# esptoy_v12.net
KiCad netlist of a schematic drawn in EAGLE
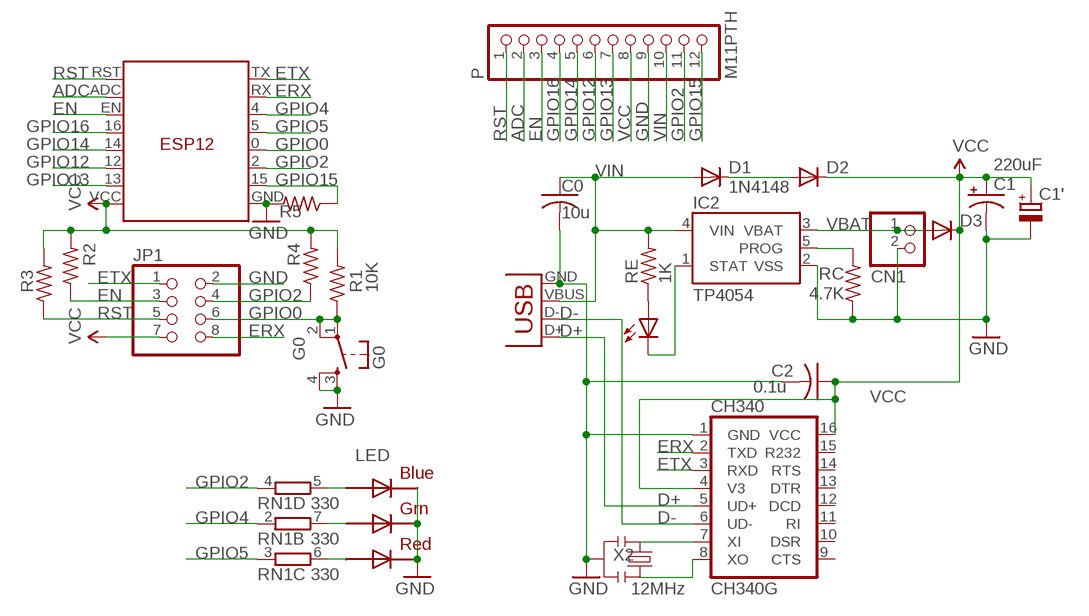
[diagram p0: schematic, sheet 1]

(export (version "E")
  (design (tool "Eeschema 10.0.6"))
  (components
    (comp (ref "C0")
      (value "10u")
      (footprint "eagle-import:C0805K")
      (libsource (lib "eagle-import") (part "adafruit2013_C-USC0805K"))
    )
    (comp (ref "C1")
      (value "220uF")
      (footprint "eagle-import:EIA3528-KIT")
      (libsource (lib "eagle-import") (part "CAP_POL3528-KIT"))
    )
    (comp (ref "C1'")
      (value "CPOL-EUD")
      (footprint "eagle-import:PANASONIC_D")
      (libsource (lib "eagle-import") (part "CPOL-EUD"))
    )
    (comp (ref "C2")
      (value "0.1u")
      (footprint "eagle-import:C0603K")
      (libsource (lib "eagle-import") (part "C-USC0603K"))
    )
    (comp (ref "CH340")
      (value "CH340G")
      (footprint "eagle-import:SO16")
      (libsource (lib "eagle-import") (part "CH340G"))
    )
    (comp (ref "CHG")
      (value "0805")
      (footprint "eagle-import:CHIPLED_0805")
      (libsource (lib "eagle-import") (part "LEDCHIPLED_0805"))
    )
    (comp (ref "CN1")
      (value "JST_2PIN-SMT-RA")
      (footprint "eagle-import:JST-PH-2-SMT-RA")
      (libsource (lib "eagle-import") (part "JST_2PIN-SMT-RA"))
    )
    (comp (ref "D1")
      (value "1N4148")
      (footprint "eagle-import:MINIMELF")
      (libsource (lib "eagle-import") (part "DIODE-MINIMELF"))
    )
    (comp (ref "D2")
      (value "DIODE-MINIMELF")
      (footprint "eagle-import:MINIMELF")
      (libsource (lib "eagle-import") (part "DIODE-MINIMELF"))
    )
    (comp (ref "D3")
      (value "DIODE-MINIMELF")
      (footprint "eagle-import:MINIMELF")
      (libsource (lib "eagle-import") (part "DIODE-MINIMELF"))
    )
    (comp (ref "G0")
      (value "G0")
      (footprint "eagle-import:TACTILE_SWITCH_SMD")
      (libsource (lib "eagle-import") (part "TAC_SWITCHSMD"))
    )
    (comp (ref "IC2")
      (value "TP4054")
      (footprint "eagle-import:SOT23-5")
      (libsource (lib "eagle-import") (part "MCP73831"))
    )
    (comp (ref "JP1")
      (value "PINHD-2X4")
      (footprint "eagle-import:2X04")
      (libsource (lib "eagle-import") (part "PINHD-2X4"))
    )
    (comp (ref "LED")
      (value "RGBLED5050")
      (footprint "eagle-import:RGBLED5050")
      (libsource (lib "eagle-import") (part "RGBLED5050"))
    )
    (comp (ref "P")
      (value "M11PTH")
      (footprint "eagle-import:1X12-CB")
      (libsource (lib "eagle-import") (part "PINHD-1X12-CB"))
    )
    (comp (ref "R1")
      (value "10K")
      (footprint "eagle-import:R0603")
      (libsource (lib "eagle-import") (part "R-US_R0603"))
    )
    (comp (ref "R2")
      (value "R-US_R0603")
      (footprint "eagle-import:R0603")
      (libsource (lib "eagle-import") (part "R-US_R0603"))
    )
    (comp (ref "R3")
      (value "R-US_R0603")
      (footprint "eagle-import:R0603")
      (libsource (lib "eagle-import") (part "R-US_R0603"))
    )
    (comp (ref "R4")
      (value "R-US_R0603")
      (footprint "eagle-import:R0603")
      (libsource (lib "eagle-import") (part "R-US_R0603"))
    )
    (comp (ref "R5")
      (value "R-US_R0603")
      (footprint "eagle-import:R0603")
      (libsource (lib "eagle-import") (part "R-US_R0603"))
    )
    (comp (ref "RC")
      (value "4.7K")
      (footprint "eagle-import:R0805")
      (libsource (lib "eagle-import") (part "adafruit2013_R-US_R0805"))
    )
    (comp (ref "RE")
      (value "1K")
      (footprint "eagle-import:R0603")
      (libsource (lib "eagle-import") (part "R-US_R0603"))
    )
    (comp (ref "RN1")
      (value "330")
      (footprint "eagle-import:EXB38V")
      (libsource (lib "eagle-import") (part "4R-NEXB38V"))
    )
    (comp (ref "U$1")
      (value "ESP12")
      (footprint "eagle-import:ESP12")
      (libsource (lib "eagle-import") (part "ESP12"))
    )
    (comp (ref "X2")
      (value "12MHz")
      (footprint "eagle-import:RESONATOR-SMD")
      (libsource (lib "eagle-import") (part "RESONATORSMD"))
    )
    (comp (ref "X3")
      (value "USB-MICROB")
      (footprint "eagle-import:USB-MICROB")
      (libsource (lib "eagle-import") (part "USB-MICROB"))
    )
  )
  (nets
    (net (code "1") (name "/ADC") (class "Default")
      (node (ref "P") (pin "2") (pinfunction "2_2") (pintype "passive"))
      (node (ref "U$1") (pin "ADC") (pinfunction "ADC_ADC") (pintype "bidirectional"))
    )
    (net (code "2") (name "/D+") (class "Default")
      (node (ref "CH340") (pin "5") (pinfunction "UD+_5") (pintype "bidirectional"))
      (node (ref "X3") (pin "D+") (pinfunction "D+_D+") (pintype "bidirectional"))
    )
    (net (code "3") (name "/D-") (class "Default")
      (node (ref "CH340") (pin "6") (pinfunction "UD-_6") (pintype "bidirectional"))
      (node (ref "X3") (pin "D-") (pinfunction "D-_D-") (pintype "bidirectional"))
    )
    (net (code "4") (name "/EN") (class "Default")
      (node (ref "JP1") (pin "3") (pinfunction "3_3") (pintype "passive"))
      (node (ref "P") (pin "3") (pinfunction "3_3") (pintype "passive"))
      (node (ref "R2") (pin "1") (pinfunction "1_1") (pintype "passive"))
      (node (ref "U$1") (pin "EN") (pinfunction "EN_EN") (pintype "bidirectional"))
    )
    (net (code "5") (name "/ERX") (class "Default")
      (node (ref "CH340") (pin "2") (pinfunction "TXD_2") (pintype "bidirectional"))
      (node (ref "JP1") (pin "8") (pinfunction "8_8") (pintype "passive"))
      (node (ref "U$1") (pin "RX") (pinfunction "RX_RX") (pintype "bidirectional"))
    )
    (net (code "6") (name "/ETX") (class "Default")
      (node (ref "CH340") (pin "3") (pinfunction "RXD_3") (pintype "bidirectional"))
      (node (ref "JP1") (pin "1") (pinfunction "1_1") (pintype "passive"))
      (node (ref "U$1") (pin "TX") (pinfunction "TX_TX") (pintype "bidirectional"))
    )
    (net (code "7") (name "/GPIO0") (class "Default")
      (node (ref "G0") (pin "1") (pinfunction "1_1") (pintype "passive"))
      (node (ref "G0") (pin "2") (pinfunction "2_2") (pintype "passive"))
      (node (ref "JP1") (pin "6") (pinfunction "6_6") (pintype "passive"))
      (node (ref "R1") (pin "1") (pinfunction "1_1") (pintype "passive"))
      (node (ref "U$1") (pin "0") (pinfunction "G0_0") (pintype "bidirectional"))
    )
    (net (code "8") (name "/GPIO2") (class "Default")
      (node (ref "JP1") (pin "4") (pinfunction "4_4") (pintype "passive"))
      (node (ref "P") (pin "11") (pinfunction "11_11") (pintype "passive"))
      (node (ref "R4") (pin "1") (pinfunction "1_1") (pintype "passive"))
      (node (ref "RN1") (pin "4") (pinfunction "1_4") (pintype "passive"))
      (node (ref "U$1") (pin "2") (pinfunction "G2_2") (pintype "bidirectional"))
    )
    (net (code "9") (name "/GPIO4") (class "Default")
      (node (ref "RN1") (pin "2") (pinfunction "1_2") (pintype "passive"))
      (node (ref "U$1") (pin "4") (pinfunction "G4_4") (pintype "bidirectional"))
    )
    (net (code "10") (name "/GPIO5") (class "Default")
      (node (ref "RN1") (pin "3") (pinfunction "1_3") (pintype "passive"))
      (node (ref "U$1") (pin "5") (pinfunction "G5_5") (pintype "bidirectional"))
    )
    (net (code "11") (name "/GPIO12") (class "Default")
      (node (ref "P") (pin "6") (pinfunction "6_6") (pintype "passive"))
      (node (ref "U$1") (pin "12") (pinfunction "G12_12") (pintype "bidirectional"))
    )
    (net (code "12") (name "/GPIO13") (class "Default")
      (node (ref "P") (pin "7") (pinfunction "7_7") (pintype "passive"))
      (node (ref "U$1") (pin "13") (pinfunction "G13_13") (pintype "bidirectional"))
    )
    (net (code "13") (name "/GPIO14") (class "Default")
      (node (ref "P") (pin "5") (pinfunction "5_5") (pintype "passive"))
      (node (ref "U$1") (pin "14") (pinfunction "G14_14") (pintype "bidirectional"))
    )
    (net (code "14") (name "/GPIO15") (class "Default")
      (node (ref "P") (pin "12") (pinfunction "12_12") (pintype "passive"))
      (node (ref "R5") (pin "1") (pinfunction "1_1") (pintype "passive"))
      (node (ref "U$1") (pin "15") (pinfunction "G15_15") (pintype "bidirectional"))
    )
    (net (code "15") (name "/GPIO16") (class "Default")
      (node (ref "P") (pin "4") (pinfunction "4_4") (pintype "passive"))
      (node (ref "U$1") (pin "16") (pinfunction "G16_16") (pintype "bidirectional"))
    )
    (net (code "16") (name "/RST") (class "Default")
      (node (ref "JP1") (pin "5") (pinfunction "5_5") (pintype "passive"))
      (node (ref "P") (pin "1") (pinfunction "1_1") (pintype "passive"))
      (node (ref "R3") (pin "1") (pinfunction "1_1") (pintype "passive"))
      (node (ref "U$1") (pin "RST") (pinfunction "RST_RST") (pintype "bidirectional"))
    )
    (net (code "17") (name "/VBAT") (class "Default")
      (node (ref "CN1") (pin "1") (pinfunction "2_1") (pintype "passive"))
      (node (ref "D3") (pin "A") (pinfunction "A_A") (pintype "passive"))
      (node (ref "IC2") (pin "3") (pinfunction "VBAT_3") (pintype "power_in"))
    )
    (net (code "18") (name "/VIN") (class "Default")
      (node (ref "C0") (pin "1") (pinfunction "1_1") (pintype "passive"))
      (node (ref "D1") (pin "A") (pinfunction "A_A") (pintype "passive"))
      (node (ref "IC2") (pin "4") (pinfunction "VIN_4") (pintype "power_in"))
      (node (ref "P") (pin "10") (pinfunction "10_10") (pintype "passive"))
      (node (ref "RE") (pin "2") (pinfunction "2_2") (pintype "passive"))
      (node (ref "X3") (pin "VBUS") (pinfunction "VBUS_VBUS") (pintype "bidirectional"))
    )
    (net (code "19") (name "GND") (class "Default")
      (node (ref "C0") (pin "2") (pinfunction "2_2") (pintype "passive"))
      (node (ref "C1") (pin "C") (pinfunction "-_C") (pintype "passive"))
      (node (ref "C1'") (pin "-") (pinfunction "-_-") (pintype "passive"))
      (node (ref "C2") (pin "2") (pinfunction "2_2") (pintype "passive"))
      (node (ref "CH340") (pin "1") (pinfunction "GND_1") (pintype "power_in"))
      (node (ref "CN1") (pin "2") (pinfunction "1_2") (pintype "passive"))
      (node (ref "G0") (pin "3") (pinfunction "3_3") (pintype "passive"))
      (node (ref "G0") (pin "4") (pinfunction "4_4") (pintype "passive"))
      (node (ref "IC2") (pin "2") (pinfunction "VSS_2") (pintype "power_in"))
      (node (ref "JP1") (pin "2") (pinfunction "2_2") (pintype "passive"))
      (node (ref "LED") (pin "4") (pinfunction "BLUE_C_4") (pintype "bidirectional"))
      (node (ref "LED") (pin "5") (pinfunction "RED_C_5") (pintype "bidirectional"))
      (node (ref "LED") (pin "6") (pinfunction "GREEN_C_6") (pintype "bidirectional"))
      (node (ref "P") (pin "9") (pinfunction "9_9") (pintype "passive"))
      (node (ref "R5") (pin "2") (pinfunction "2_2") (pintype "passive"))
      (node (ref "RC") (pin "1") (pinfunction "1_1") (pintype "passive"))
      (node (ref "U$1") (pin "GND") (pinfunction "GND_GND") (pintype "power_in"))
      (node (ref "X2") (pin "2") (pinfunction "2_2") (pintype "passive"))
      (node (ref "X3") (pin "GND") (pinfunction "GND_GND") (pintype "bidirectional"))
    )
    (net (code "20") (name "Net-(CH340-XI)") (class "Default")
      (node (ref "CH340") (pin "7") (pinfunction "XI_7") (pintype "bidirectional"))
      (node (ref "X2") (pin "1") (pinfunction "1_1") (pintype "passive"))
    )
    (net (code "21") (name "Net-(CH340-XO)") (class "Default")
      (node (ref "CH340") (pin "8") (pinfunction "XO_8") (pintype "bidirectional"))
      (node (ref "X2") (pin "3") (pinfunction "3_3") (pintype "passive"))
    )
    (net (code "22") (name "Net-(CHG-PadA)") (class "Default")
      (node (ref "CHG") (pin "A") (pinfunction "A_A") (pintype "passive"))
      (node (ref "RE") (pin "1") (pinfunction "1_1") (pintype "passive"))
    )
    (net (code "23") (name "Net-(D1-PadC)") (class "Default")
      (node (ref "D1") (pin "C") (pinfunction "C_C") (pintype "passive"))
      (node (ref "D2") (pin "A") (pinfunction "A_A") (pintype "passive"))
    )
    (net (code "24") (name "Net-(IC2-PROG)") (class "Default")
      (node (ref "IC2") (pin "5") (pinfunction "PROG_5") (pintype "input"))
      (node (ref "RC") (pin "2") (pinfunction "2_2") (pintype "passive"))
    )
    (net (code "25") (name "Net-(IC2-STAT)") (class "Default")
      (node (ref "CHG") (pin "C") (pinfunction "C_C") (pintype "passive"))
      (node (ref "IC2") (pin "1") (pinfunction "STAT_1") (pintype "output"))
    )
    (net (code "26") (name "Net-(LED-BLUE_A)") (class "Default")
      (node (ref "LED") (pin "3") (pinfunction "BLUE_A_3") (pintype "bidirectional"))
      (node (ref "RN1") (pin "5") (pinfunction "2_5") (pintype "passive"))
    )
    (net (code "27") (name "Net-(LED-GREEN_A)") (class "Default")
      (node (ref "LED") (pin "1") (pinfunction "GREEN_A_1") (pintype "bidirectional"))
      (node (ref "RN1") (pin "7") (pinfunction "2_7") (pintype "passive"))
    )
    (net (code "28") (name "Net-(LED-RED_A)") (class "Default")
      (node (ref "LED") (pin "2") (pinfunction "RED_A_2") (pintype "bidirectional"))
      (node (ref "RN1") (pin "6") (pinfunction "2_6") (pintype "passive"))
    )
    (net (code "29") (name "VCC") (class "Default")
      (node (ref "C1") (pin "A") (pinfunction "+_A") (pintype "passive"))
      (node (ref "C1'") (pin "+") (pinfunction "+_+") (pintype "passive"))
      (node (ref "C2") (pin "1") (pinfunction "1_1") (pintype "passive"))
      (node (ref "CH340") (pin "16") (pinfunction "VCC_16") (pintype "power_in"))
      (node (ref "CH340") (pin "4") (pinfunction "V3_4") (pintype "bidirectional"))
      (node (ref "D2") (pin "C") (pinfunction "C_C") (pintype "passive"))
      (node (ref "D3") (pin "C") (pinfunction "C_C") (pintype "passive"))
      (node (ref "JP1") (pin "7") (pinfunction "7_7") (pintype "passive"))
      (node (ref "P") (pin "8") (pinfunction "8_8") (pintype "passive"))
      (node (ref "R1") (pin "2") (pinfunction "2_2") (pintype "passive"))
      (node (ref "R2") (pin "2") (pinfunction "2_2") (pintype "passive"))
      (node (ref "R3") (pin "2") (pinfunction "2_2") (pintype "passive"))
      (node (ref "R4") (pin "2") (pinfunction "2_2") (pintype "passive"))
      (node (ref "U$1") (pin "VCC") (pinfunction "VCC_VCC") (pintype "power_in"))
    )
    (net (code "30") (name "unconnected-(CH340-CTS-Pad9)") (class "Default")
      (node (ref "CH340") (pin "9") (pinfunction "CTS_9") (pintype "bidirectional"))
    )
    (net (code "31") (name "unconnected-(CH340-DCD-Pad12)") (class "Default")
      (node (ref "CH340") (pin "12") (pinfunction "DCD_12") (pintype "bidirectional"))
    )
    (net (code "32") (name "unconnected-(CH340-DSR-Pad10)") (class "Default")
      (node (ref "CH340") (pin "10") (pinfunction "DSR_10") (pintype "bidirectional"))
    )
    (net (code "33") (name "unconnected-(CH340-DTR-Pad13)") (class "Default")
      (node (ref "CH340") (pin "13") (pinfunction "DTR_13") (pintype "bidirectional"))
    )
    (net (code "34") (name "unconnected-(CH340-R232-Pad15)") (class "Default")
      (node (ref "CH340") (pin "15") (pinfunction "R232_15") (pintype "bidirectional"))
    )
    (net (code "35") (name "unconnected-(CH340-RI-Pad11)") (class "Default")
      (node (ref "CH340") (pin "11") (pinfunction "RI_11") (pintype "bidirectional"))
    )
    (net (code "36") (name "unconnected-(CH340-RTS-Pad14)") (class "Default")
      (node (ref "CH340") (pin "14") (pinfunction "RTS_14") (pintype "bidirectional"))
    )
  )
)
